# MicrocontrollerPorts.net
KiCad netlist of a schematic drawn in Altium Designer
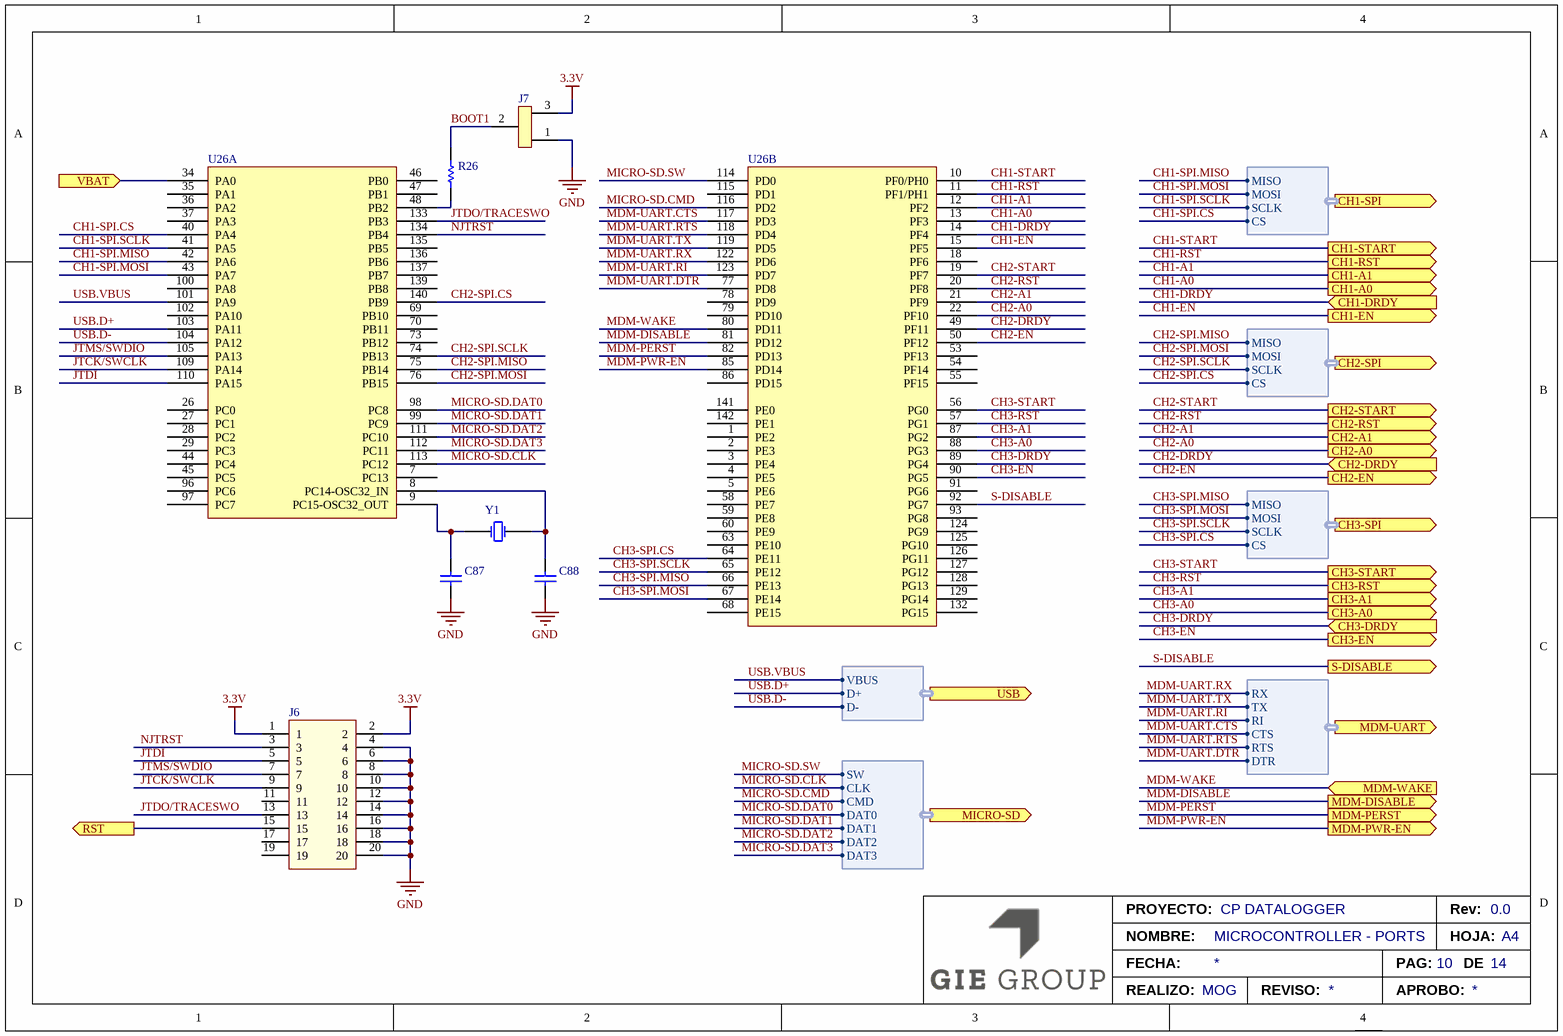
[diagram p0: MicrocontrollerPorts.SchDoc]

(export (version "E")
  (design (tool "Eeschema 10.0.6"))
  (components
    (comp (ref "C87")
      (value "CBR06C679B5GAC")
      (footprint "CAP-0603")
      (description "CAP CER 6.7 pF 50V C0G 0603")
      (fields (field (name "MANUFACTURER") "Kemet") (field (name "TOLERANCE") "+/-0.1pF"))
      (libsource (lib "Kemet") (part "CBR06C679B5GAC"))
    )
    (comp (ref "C88")
      (value "CBR06C679B5GAC")
      (footprint "CAP-0603")
      (description "CAP CER 6.7 pF 50V C0G 0603")
      (fields (field (name "MANUFACTURER") "Kemet") (field (name "TOLERANCE") "+/-0.1pF"))
      (libsource (lib "Kemet") (part "CBR06C679B5GAC"))
    )
    (comp (ref "J6")
      (value "~")
      (footprint "TE-5103308-5")
      (description "CONN HEADER VERT 20POS 2.54MM")
      (libsource (lib "TeConnectivity") (part "5103308-5"))
    )
    (comp (ref "J7")
      (value "PRPC003SAAN-RC")
      (footprint "PIN3")
      (description "CONN HEADER .100\" SNGL STR 3POS")
      (fields (field (name "MANUFACTURER") "Sullins Connector Solutions"))
      (libsource (lib "Sullins") (part "PRPC003SAAN-RC"))
    )
    (comp (ref "R26")
      (value "RC0603FR-07100KL")
      (footprint "RES-0603")
      (description "RES SMD 100K OHM 1% 1/10W 0603")
      (fields (field (name "TOLERANCE") "1%") (field (name "MANUFACTURER") "Yageo"))
      (libsource (lib "Yageo") (part "RC0603FR-07100KL"))
    )
    (comp (ref "U26")
      (value "STM32F429ZIT6")
      (footprint "LQFP144")
      (description "IC MCU 32BIT 2MB FLASH 144LQFP")
      (fields (field (name "MANUFACTURER") "STMicroelectronics"))
      (libsource (lib "STMicroelectronics") (part "STM32F429ZIT6"))
    )
    (comp (ref "Y1")
      (value "ABS07-32.768KHZ-7-T")
      (footprint "XTAL-ABS07")
      (description "CRYSTAL 32.768KHZ 7PF SMD")
      (fields (field (name "MANUFACTURER") "Abracon"))
      (libsource (lib "Abracon") (part "ABS07-32.768KHZ-7-T"))
    )
  )
  (nets
    (net (code "7") (name "/BOOT1") (class "Default")
      (node (ref "J7") (pin "2") (pinfunction "2_2") (pintype "passive"))
      (node (ref "R26") (pin "2") (pinfunction "2_2") (pintype "passive"))
    )
    (net (code "8") (name "/CH1-A0") (class "Default")
      (node (ref "U26") (pin "13") (pinfunction "PF3_13") (pintype "passive"))
    )
    (net (code "9") (name "/CH1-A1") (class "Default")
      (node (ref "U26") (pin "12") (pinfunction "PF2_12") (pintype "passive"))
    )
    (net (code "10") (name "/CH1-DRDY") (class "Default")
      (node (ref "U26") (pin "14") (pinfunction "PF4_14") (pintype "passive"))
    )
    (net (code "11") (name "/CH1-EN") (class "Default")
      (node (ref "U26") (pin "15") (pinfunction "PF5_15") (pintype "passive"))
    )
    (net (code "12") (name "/CH1-RST") (class "Default")
      (node (ref "U26") (pin "11") (pinfunction "PF1/PH1_11") (pintype "passive"))
    )
    (net (code "13") (name "/CH1-SPI.CS") (class "Default")
      (node (ref "U26") (pin "40") (pinfunction "PA4_40") (pintype "passive"))
    )
    (net (code "14") (name "/CH1-SPI.MISO") (class "Default")
      (node (ref "U26") (pin "42") (pinfunction "PA6_42") (pintype "passive"))
    )
    (net (code "15") (name "/CH1-SPI.MOSI") (class "Default")
      (node (ref "U26") (pin "43") (pinfunction "PA7_43") (pintype "passive"))
    )
    (net (code "16") (name "/CH1-SPI.SCLK") (class "Default")
      (node (ref "U26") (pin "41") (pinfunction "PA5_41") (pintype "passive"))
    )
    (net (code "17") (name "/CH1-START") (class "Default")
      (node (ref "U26") (pin "10") (pinfunction "PF0/PH0_10") (pintype "passive"))
    )
    (net (code "18") (name "/CH2-A0") (class "Default")
      (node (ref "U26") (pin "22") (pinfunction "PF10_22") (pintype "passive"))
    )
    (net (code "19") (name "/CH2-A1") (class "Default")
      (node (ref "U26") (pin "21") (pinfunction "PF9_21") (pintype "passive"))
    )
    (net (code "20") (name "/CH2-DRDY") (class "Default")
      (node (ref "U26") (pin "49") (pinfunction "PF11_49") (pintype "passive"))
    )
    (net (code "21") (name "/CH2-EN") (class "Default")
      (node (ref "U26") (pin "50") (pinfunction "PF12_50") (pintype "passive"))
    )
    (net (code "22") (name "/CH2-RST") (class "Default")
      (node (ref "U26") (pin "20") (pinfunction "PF8_20") (pintype "passive"))
    )
    (net (code "23") (name "/CH2-SPI.CS") (class "Default")
      (node (ref "U26") (pin "140") (pinfunction "PB9_140") (pintype "passive"))
    )
    (net (code "24") (name "/CH2-SPI.MISO") (class "Default")
      (node (ref "U26") (pin "75") (pinfunction "PB14_75") (pintype "passive"))
    )
    (net (code "25") (name "/CH2-SPI.MOSI") (class "Default")
      (node (ref "U26") (pin "76") (pinfunction "PB15_76") (pintype "passive"))
    )
    (net (code "26") (name "/CH2-SPI.SCLK") (class "Default")
      (node (ref "U26") (pin "74") (pinfunction "PB13_74") (pintype "passive"))
    )
    (net (code "27") (name "/CH2-START") (class "Default")
      (node (ref "U26") (pin "19") (pinfunction "PF7_19") (pintype "passive"))
    )
    (net (code "28") (name "/CH3-A0") (class "Default")
      (node (ref "U26") (pin "88") (pinfunction "PG3_88") (pintype "passive"))
    )
    (net (code "29") (name "/CH3-A1") (class "Default")
      (node (ref "U26") (pin "87") (pinfunction "PG2_87") (pintype "passive"))
    )
    (net (code "30") (name "/CH3-DRDY") (class "Default")
      (node (ref "U26") (pin "89") (pinfunction "PG4_89") (pintype "passive"))
    )
    (net (code "31") (name "/CH3-EN") (class "Default")
      (node (ref "U26") (pin "90") (pinfunction "PG5_90") (pintype "passive"))
    )
    (net (code "32") (name "/CH3-RST") (class "Default")
      (node (ref "U26") (pin "57") (pinfunction "PG1_57") (pintype "passive"))
    )
    (net (code "33") (name "/CH3-SPI.CS") (class "Default")
      (node (ref "U26") (pin "64") (pinfunction "PE11_64") (pintype "passive"))
    )
    (net (code "34") (name "/CH3-SPI.MISO") (class "Default")
      (node (ref "U26") (pin "66") (pinfunction "PE13_66") (pintype "passive"))
    )
    (net (code "35") (name "/CH3-SPI.MOSI") (class "Default")
      (node (ref "U26") (pin "67") (pinfunction "PE14_67") (pintype "passive"))
    )
    (net (code "36") (name "/CH3-SPI.SCLK") (class "Default")
      (node (ref "U26") (pin "65") (pinfunction "PE12_65") (pintype "passive"))
    )
    (net (code "37") (name "/CH3-START") (class "Default")
      (node (ref "U26") (pin "56") (pinfunction "PG0_56") (pintype "passive"))
    )
    (net (code "38") (name "/JTCK{slash}SWCLK") (class "Default")
      (node (ref "J6") (pin "9") (pinfunction "9_9") (pintype "passive"))
      (node (ref "U26") (pin "109") (pinfunction "PA14_109") (pintype "passive"))
    )
    (net (code "39") (name "/JTDI") (class "Default")
      (node (ref "J6") (pin "5") (pinfunction "5_5") (pintype "passive"))
      (node (ref "U26") (pin "110") (pinfunction "PA15_110") (pintype "passive"))
    )
    (net (code "40") (name "/JTDO{slash}TRACESWO") (class "Default")
      (node (ref "J6") (pin "13") (pinfunction "13_13") (pintype "passive"))
      (node (ref "U26") (pin "133") (pinfunction "PB3_133") (pintype "passive"))
    )
    (net (code "41") (name "/JTMS{slash}SWDIO") (class "Default")
      (node (ref "J6") (pin "7") (pinfunction "7_7") (pintype "passive"))
      (node (ref "U26") (pin "105") (pinfunction "PA13_105") (pintype "passive"))
    )
    (net (code "42") (name "/MDM-DISABLE") (class "Default")
      (node (ref "U26") (pin "81") (pinfunction "PD12_81") (pintype "passive"))
    )
    (net (code "43") (name "/MDM-PERST") (class "Default")
      (node (ref "U26") (pin "82") (pinfunction "PD13_82") (pintype "passive"))
    )
    (net (code "44") (name "/MDM-PWR-EN") (class "Default")
      (node (ref "U26") (pin "85") (pinfunction "PD14_85") (pintype "passive"))
    )
    (net (code "45") (name "/MDM-UART.CTS") (class "Default")
      (node (ref "U26") (pin "117") (pinfunction "PD3_117") (pintype "passive"))
    )
    (net (code "46") (name "/MDM-UART.DTR") (class "Default")
      (node (ref "U26") (pin "77") (pinfunction "PD8_77") (pintype "passive"))
    )
    (net (code "47") (name "/MDM-UART.RI") (class "Default")
      (node (ref "U26") (pin "123") (pinfunction "PD7_123") (pintype "passive"))
    )
    (net (code "48") (name "/MDM-UART.RTS") (class "Default")
      (node (ref "U26") (pin "118") (pinfunction "PD4_118") (pintype "passive"))
    )
    (net (code "49") (name "/MDM-UART.RX") (class "Default")
      (node (ref "U26") (pin "122") (pinfunction "PD6_122") (pintype "passive"))
    )
    (net (code "50") (name "/MDM-UART.TX") (class "Default")
      (node (ref "U26") (pin "119") (pinfunction "PD5_119") (pintype "passive"))
    )
    (net (code "51") (name "/MDM-WAKE") (class "Default")
      (node (ref "U26") (pin "80") (pinfunction "PD11_80") (pintype "passive"))
    )
    (net (code "52") (name "/MICRO-SD.CLK") (class "Default")
      (node (ref "U26") (pin "113") (pinfunction "PC12_113") (pintype "passive"))
    )
    (net (code "53") (name "/MICRO-SD.CMD") (class "Default")
      (node (ref "U26") (pin "116") (pinfunction "PD2_116") (pintype "passive"))
    )
    (net (code "54") (name "/MICRO-SD.DAT0") (class "Default")
      (node (ref "U26") (pin "98") (pinfunction "PC8_98") (pintype "passive"))
    )
    (net (code "55") (name "/MICRO-SD.DAT1") (class "Default")
      (node (ref "U26") (pin "99") (pinfunction "PC9_99") (pintype "passive"))
    )
    (net (code "56") (name "/MICRO-SD.DAT2") (class "Default")
      (node (ref "U26") (pin "111") (pinfunction "PC10_111") (pintype "passive"))
    )
    (net (code "57") (name "/MICRO-SD.DAT3") (class "Default")
      (node (ref "U26") (pin "112") (pinfunction "PC11_112") (pintype "passive"))
    )
    (net (code "58") (name "/MICRO-SD.SW") (class "Default")
      (node (ref "U26") (pin "114") (pinfunction "PD0_114") (pintype "passive"))
    )
    (net (code "59") (name "/NJTRST") (class "Default")
      (node (ref "J6") (pin "3") (pinfunction "3_3") (pintype "passive"))
      (node (ref "U26") (pin "134") (pinfunction "PB4_134") (pintype "passive"))
    )
    (net (code "60") (name "/RST") (class "Default")
      (node (ref "J6") (pin "15") (pinfunction "15_15") (pintype "passive"))
    )
    (net (code "61") (name "/S-DISABLE") (class "Default")
      (node (ref "U26") (pin "92") (pinfunction "PG7_92") (pintype "passive"))
    )
    (net (code "62") (name "/USB.D+") (class "Default")
      (node (ref "U26") (pin "103") (pinfunction "PA11_103") (pintype "passive"))
    )
    (net (code "63") (name "/USB.D-") (class "Default")
      (node (ref "U26") (pin "104") (pinfunction "PA12_104") (pintype "passive"))
    )
    (net (code "64") (name "/USB.VBUS") (class "Default")
      (node (ref "U26") (pin "101") (pinfunction "PA9_101") (pintype "passive"))
    )
    (net (code "65") (name "/VBAT") (class "Default")
      (node (ref "U26") (pin "34") (pinfunction "PA0_34") (pintype "passive"))
    )
    (net (code "72") (name "3.3V") (class "Default")
      (node (ref "J6") (pin "1") (pinfunction "1_1") (pintype "passive"))
      (node (ref "J6") (pin "2") (pinfunction "2_2") (pintype "passive"))
      (node (ref "J7") (pin "3") (pinfunction "3_3") (pintype "passive"))
    )
    (net (code "73") (name "GND") (class "Default")
      (node (ref "C87") (pin "1") (pinfunction "1_1") (pintype "passive"))
      (node (ref "C88") (pin "1") (pinfunction "1_1") (pintype "passive"))
      (node (ref "J6") (pin "10") (pinfunction "10_10") (pintype "passive"))
      (node (ref "J6") (pin "12") (pinfunction "12_12") (pintype "passive"))
      (node (ref "J6") (pin "14") (pinfunction "14_14") (pintype "passive"))
      (node (ref "J6") (pin "16") (pinfunction "16_16") (pintype "passive"))
      (node (ref "J6") (pin "18") (pinfunction "18_18") (pintype "passive"))
      (node (ref "J6") (pin "20") (pinfunction "20_20") (pintype "passive"))
      (node (ref "J6") (pin "4") (pinfunction "4_4") (pintype "passive"))
      (node (ref "J6") (pin "6") (pinfunction "6_6") (pintype "passive"))
      (node (ref "J6") (pin "8") (pinfunction "8_8") (pintype "passive"))
      (node (ref "J7") (pin "1") (pinfunction "1_1") (pintype "passive"))
    )
    (net (code "74") (name "Net-(U26A-PB2)") (class "Default")
      (node (ref "R26") (pin "1") (pinfunction "1_1") (pintype "passive"))
      (node (ref "U26") (pin "48") (pinfunction "PB2_48") (pintype "passive"))
    )
    (net (code "75") (name "Net-(U26A-PC14-OSC32_IN)") (class "Default")
      (node (ref "C88") (pin "2") (pinfunction "2_2") (pintype "passive"))
      (node (ref "U26") (pin "8") (pinfunction "PC14-OSC32_IN_8") (pintype "passive"))
      (node (ref "Y1") (pin "1") (pinfunction "OSC1_1") (pintype "passive"))
    )
    (net (code "76") (name "Net-(U26A-PC15-OSC32_OUT)") (class "Default")
      (node (ref "C87") (pin "2") (pinfunction "2_2") (pintype "passive"))
      (node (ref "U26") (pin "9") (pinfunction "PC15-OSC32_OUT_9") (pintype "passive"))
      (node (ref "Y1") (pin "2") (pinfunction "OSC2_2") (pintype "passive"))
    )
    (net (code "77") (name "unconnected-(J6-Pad11)") (class "Default")
      (node (ref "J6") (pin "11") (pinfunction "11_11") (pintype "passive"))
    )
    (net (code "78") (name "unconnected-(J6-Pad17)") (class "Default")
      (node (ref "J6") (pin "17") (pinfunction "17_17") (pintype "passive"))
    )
    (net (code "79") (name "unconnected-(J6-Pad19)") (class "Default")
      (node (ref "J6") (pin "19") (pinfunction "19_19") (pintype "passive"))
    )
    (net (code "80") (name "unconnected-(U26A-PA1-Pad35)") (class "Default")
      (node (ref "U26") (pin "35") (pinfunction "PA1_35") (pintype "passive"))
    )
    (net (code "81") (name "unconnected-(U26A-PA2-Pad36)") (class "Default")
      (node (ref "U26") (pin "36") (pinfunction "PA2_36") (pintype "passive"))
    )
    (net (code "82") (name "unconnected-(U26A-PA3-Pad37)") (class "Default")
      (node (ref "U26") (pin "37") (pinfunction "PA3_37") (pintype "passive"))
    )
    (net (code "83") (name "unconnected-(U26A-PA8-Pad100)") (class "Default")
      (node (ref "U26") (pin "100") (pinfunction "PA8_100") (pintype "passive"))
    )
    (net (code "84") (name "unconnected-(U26A-PA10-Pad102)") (class "Default")
      (node (ref "U26") (pin "102") (pinfunction "PA10_102") (pintype "passive"))
    )
    (net (code "85") (name "unconnected-(U26A-PB0-Pad46)") (class "Default")
      (node (ref "U26") (pin "46") (pinfunction "PB0_46") (pintype "passive"))
    )
    (net (code "86") (name "unconnected-(U26A-PB1-Pad47)") (class "Default")
      (node (ref "U26") (pin "47") (pinfunction "PB1_47") (pintype "passive"))
    )
    (net (code "87") (name "unconnected-(U26A-PB5-Pad135)") (class "Default")
      (node (ref "U26") (pin "135") (pinfunction "PB5_135") (pintype "passive"))
    )
    (net (code "88") (name "unconnected-(U26A-PB6-Pad136)") (class "Default")
      (node (ref "U26") (pin "136") (pinfunction "PB6_136") (pintype "passive"))
    )
    (net (code "89") (name "unconnected-(U26A-PB7-Pad137)") (class "Default")
      (node (ref "U26") (pin "137") (pinfunction "PB7_137") (pintype "passive"))
    )
    (net (code "90") (name "unconnected-(U26A-PB8-Pad139)") (class "Default")
      (node (ref "U26") (pin "139") (pinfunction "PB8_139") (pintype "passive"))
    )
    (net (code "91") (name "unconnected-(U26A-PB10-Pad69)") (class "Default")
      (node (ref "U26") (pin "69") (pinfunction "PB10_69") (pintype "passive"))
    )
    (net (code "92") (name "unconnected-(U26A-PB11-Pad70)") (class "Default")
      (node (ref "U26") (pin "70") (pinfunction "PB11_70") (pintype "passive"))
    )
    (net (code "93") (name "unconnected-(U26A-PB12-Pad73)") (class "Default")
      (node (ref "U26") (pin "73") (pinfunction "PB12_73") (pintype "passive"))
    )
    (net (code "94") (name "unconnected-(U26A-PC0-Pad26)") (class "Default")
      (node (ref "U26") (pin "26") (pinfunction "PC0_26") (pintype "passive"))
    )
    (net (code "95") (name "unconnected-(U26A-PC1-Pad27)") (class "Default")
      (node (ref "U26") (pin "27") (pinfunction "PC1_27") (pintype "passive"))
    )
    (net (code "96") (name "unconnected-(U26A-PC2-Pad28)") (class "Default")
      (node (ref "U26") (pin "28") (pinfunction "PC2_28") (pintype "passive"))
    )
    (net (code "97") (name "unconnected-(U26A-PC3-Pad29)") (class "Default")
      (node (ref "U26") (pin "29") (pinfunction "PC3_29") (pintype "passive"))
    )
    (net (code "98") (name "unconnected-(U26A-PC4-Pad44)") (class "Default")
      (node (ref "U26") (pin "44") (pinfunction "PC4_44") (pintype "passive"))
    )
    (net (code "99") (name "unconnected-(U26A-PC5-Pad45)") (class "Default")
      (node (ref "U26") (pin "45") (pinfunction "PC5_45") (pintype "passive"))
    )
    (net (code "100") (name "unconnected-(U26A-PC6-Pad96)") (class "Default")
      (node (ref "U26") (pin "96") (pinfunction "PC6_96") (pintype "passive"))
    )
    (net (code "101") (name "unconnected-(U26A-PC7-Pad97)") (class "Default")
      (node (ref "U26") (pin "97") (pinfunction "PC7_97") (pintype "passive"))
    )
    (net (code "102") (name "unconnected-(U26A-PC13-Pad7)") (class "Default")
      (node (ref "U26") (pin "7") (pinfunction "PC13_7") (pintype "passive"))
    )
    (net (code "103") (name "unconnected-(U26B-PD1-Pad115)") (class "Default")
      (node (ref "U26") (pin "115") (pinfunction "PD1_115") (pintype "passive"))
    )
    (net (code "104") (name "unconnected-(U26B-PD9-Pad78)") (class "Default")
      (node (ref "U26") (pin "78") (pinfunction "PD9_78") (pintype "passive"))
    )
    (net (code "105") (name "unconnected-(U26B-PD10-Pad79)") (class "Default")
      (node (ref "U26") (pin "79") (pinfunction "PD10_79") (pintype "passive"))
    )
    (net (code "106") (name "unconnected-(U26B-PD15-Pad86)") (class "Default")
      (node (ref "U26") (pin "86") (pinfunction "PD15_86") (pintype "passive"))
    )
    (net (code "107") (name "unconnected-(U26B-PE0-Pad141)") (class "Default")
      (node (ref "U26") (pin "141") (pinfunction "PE0_141") (pintype "passive"))
    )
    (net (code "108") (name "unconnected-(U26B-PE1-Pad142)") (class "Default")
      (node (ref "U26") (pin "142") (pinfunction "PE1_142") (pintype "passive"))
    )
    (net (code "109") (name "unconnected-(U26B-PE2-Pad1)") (class "Default")
      (node (ref "U26") (pin "1") (pinfunction "PE2_1") (pintype "passive"))
    )
    (net (code "110") (name "unconnected-(U26B-PE3-Pad2)") (class "Default")
      (node (ref "U26") (pin "2") (pinfunction "PE3_2") (pintype "passive"))
    )
    (net (code "111") (name "unconnected-(U26B-PE4-Pad3)") (class "Default")
      (node (ref "U26") (pin "3") (pinfunction "PE4_3") (pintype "passive"))
    )
    (net (code "112") (name "unconnected-(U26B-PE5-Pad4)") (class "Default")
      (node (ref "U26") (pin "4") (pinfunction "PE5_4") (pintype "passive"))
    )
    (net (code "113") (name "unconnected-(U26B-PE6-Pad5)") (class "Default")
      (node (ref "U26") (pin "5") (pinfunction "PE6_5") (pintype "passive"))
    )
    (net (code "114") (name "unconnected-(U26B-PE7-Pad58)") (class "Default")
      (node (ref "U26") (pin "58") (pinfunction "PE7_58") (pintype "passive"))
    )
    (net (code "115") (name "unconnected-(U26B-PE8-Pad59)") (class "Default")
      (node (ref "U26") (pin "59") (pinfunction "PE8_59") (pintype "passive"))
    )
    (net (code "116") (name "unconnected-(U26B-PE9-Pad60)") (class "Default")
      (node (ref "U26") (pin "60") (pinfunction "PE9_60") (pintype "passive"))
    )
    (net (code "117") (name "unconnected-(U26B-PE10-Pad63)") (class "Default")
      (node (ref "U26") (pin "63") (pinfunction "PE10_63") (pintype "passive"))
    )
    (net (code "118") (name "unconnected-(U26B-PE15-Pad68)") (class "Default")
      (node (ref "U26") (pin "68") (pinfunction "PE15_68") (pintype "passive"))
    )
    (net (code "119") (name "unconnected-(U26B-PF6-Pad18)") (class "Default")
      (node (ref "U26") (pin "18") (pinfunction "PF6_18") (pintype "passive"))
    )
    (net (code "120") (name "unconnected-(U26B-PF13-Pad53)") (class "Default")
      (node (ref "U26") (pin "53") (pinfunction "PF13_53") (pintype "passive"))
    )
    (net (code "121") (name "unconnected-(U26B-PF14-Pad54)") (class "Default")
      (node (ref "U26") (pin "54") (pinfunction "PF14_54") (pintype "passive"))
    )
    (net (code "122") (name "unconnected-(U26B-PF15-Pad55)") (class "Default")
      (node (ref "U26") (pin "55") (pinfunction "PF15_55") (pintype "passive"))
    )
    (net (code "123") (name "unconnected-(U26B-PG6-Pad91)") (class "Default")
      (node (ref "U26") (pin "91") (pinfunction "PG6_91") (pintype "passive"))
    )
    (net (code "124") (name "unconnected-(U26B-PG8-Pad93)") (class "Default")
      (node (ref "U26") (pin "93") (pinfunction "PG8_93") (pintype "passive"))
    )
    (net (code "125") (name "unconnected-(U26B-PG9-Pad124)") (class "Default")
      (node (ref "U26") (pin "124") (pinfunction "PG9_124") (pintype "passive"))
    )
    (net (code "126") (name "unconnected-(U26B-PG10-Pad125)") (class "Default")
      (node (ref "U26") (pin "125") (pinfunction "PG10_125") (pintype "passive"))
    )
    (net (code "127") (name "unconnected-(U26B-PG11-Pad126)") (class "Default")
      (node (ref "U26") (pin "126") (pinfunction "PG11_126") (pintype "passive"))
    )
    (net (code "128") (name "unconnected-(U26B-PG12-Pad127)") (class "Default")
      (node (ref "U26") (pin "127") (pinfunction "PG12_127") (pintype "passive"))
    )
    (net (code "129") (name "unconnected-(U26B-PG13-Pad128)") (class "Default")
      (node (ref "U26") (pin "128") (pinfunction "PG13_128") (pintype "passive"))
    )
    (net (code "130") (name "unconnected-(U26B-PG14-Pad129)") (class "Default")
      (node (ref "U26") (pin "129") (pinfunction "PG14_129") (pintype "passive"))
    )
    (net (code "131") (name "unconnected-(U26B-PG15-Pad132)") (class "Default")
      (node (ref "U26") (pin "132") (pinfunction "PG15_132") (pintype "passive"))
    )
  )
)
